# Sheet1.net
KiCad netlist of a schematic drawn in Altium Designer
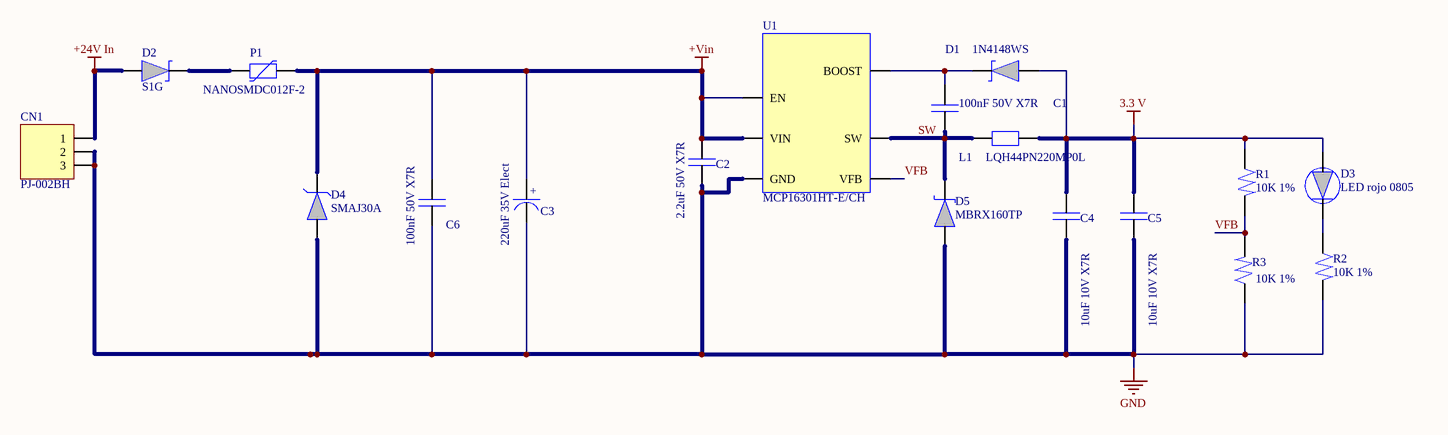
[diagram p0: Sheet1.SchDoc]

(export (version "E")
  (design (tool "Eeschema 10.0.6"))
  (components
    (comp (ref "C1")
      (value "100nF 50V X7R")
      (description "Capacitor AF")
      (libsource (lib "Schlib1") (part "CAPACITOR"))
    )
    (comp (ref "C2")
      (value "2.2uF 50V X7R")
      (description "Capacitor AF")
      (libsource (lib "Schlib1") (part "CAPACITOR"))
    )
    (comp (ref "C3")
      (value "220uF 35V Elect")
      (description "Capacitor polarizado")
      (libsource (lib "Schlib1") (part "POL_CAP"))
    )
    (comp (ref "C4")
      (value "10uF 10V X7R")
      (description "Capacitor AF")
      (libsource (lib "Schlib1") (part "CAPACITOR"))
    )
    (comp (ref "C5")
      (value "10uF 10V X7R")
      (description "Capacitor AF")
      (libsource (lib "Schlib1") (part "CAPACITOR"))
    )
    (comp (ref "C6")
      (value "100nF 50V X7R")
      (description "Capacitor AF")
      (libsource (lib "Schlib1") (part "CAPACITOR"))
    )
    (comp (ref "CN1") (value "PJ-002BH") (libsource (lib "Schlib1") (part "Connector")))
    (comp (ref "D1") (value "1N4148WS") (libsource (lib "Schlib1") (part "TVS_DIODE")))
    (comp (ref "D2") (value "S1G") (libsource (lib "Schlib1") (part "TVS_DIODE")))
    (comp (ref "D3") (value "LED rojo 0805") (libsource (lib "Schlib1") (part "LED_DIODE")))
    (comp (ref "D4") (value "SMAJ30A") (libsource (lib "Schlib1") (part "ZENER_DIODE")))
    (comp (ref "D5") (value "MBRX160TP") (libsource (lib "Schlib1") (part "TVS_DIODE")))
    (comp (ref "L1")
      (value "LQH44PN220MP0L")
      (description "Inductor")
      (libsource (lib "Schlib1") (part "Inductor"))
    )
    (comp (ref "P1")
      (value "NANOSMDC012F-2")
      (description "Polyswitch")
      (libsource (lib "Schlib1") (part "Polyswitch"))
    )
    (comp (ref "R1") (value "10K 1%") (libsource (lib "Schlib1") (part "Resistor")))
    (comp (ref "R2") (value "10K 1%") (libsource (lib "Schlib1") (part "Resistor")))
    (comp (ref "R3") (value "10K 1%") (libsource (lib "Schlib1") (part "Resistor")))
    (comp (ref "U1")
      (value "MCP16301HT-E/CH")
      (description "Driver Switching")
      (libsource (lib "Schlib1") (part "Integrado"))
    )
  )
  (nets
    (net (code "1") (name "+24V In") (class "Default")
      (node (ref "CN1") (pin "42") (pinfunction "1_42") (pintype "passive"))
      (node (ref "D2") (pin "34") (pinfunction "34_34") (pintype "passive"))
    )
    (net (code "2") (name "+Vin") (class "Default")
      (node (ref "C2") (pin "39") (pinfunction "39_39") (pintype "passive"))
      (node (ref "C3") (pin "36") (pinfunction "36_36") (pintype "passive"))
      (node (ref "C6") (pin "39") (pinfunction "39_39") (pintype "passive"))
      (node (ref "D4") (pin "33") (pinfunction "33_33") (pintype "passive"))
      (node (ref "P1") (pin "40") (pinfunction "40_40") (pintype "passive"))
      (node (ref "U1") (pin "49") (pinfunction "EN_49") (pintype "passive"))
      (node (ref "U1") (pin "50") (pinfunction "VIN_50") (pintype "passive"))
    )
    (net (code "3") (name "/SW") (class "Default")
      (node (ref "C1") (pin "38") (pinfunction "38_38") (pintype "passive"))
      (node (ref "D5") (pin "35") (pinfunction "35_35") (pintype "passive"))
      (node (ref "L1") (pin "45") (pinfunction "45_45") (pintype "passive"))
      (node (ref "U1") (pin "52") (pinfunction "SW_52") (pintype "passive"))
    )
    (net (code "4") (name "/VFB") (class "Default")
      (node (ref "R1") (pin "48") (pinfunction "48_48") (pintype "passive"))
      (node (ref "R3") (pin "48") (pinfunction "48_48") (pintype "passive"))
      (node (ref "U1") (pin "54") (pinfunction "VFB_54") (pintype "passive"))
    )
    (net (code "5") (name "3.3 V") (class "Default")
      (node (ref "C4") (pin "39") (pinfunction "39_39") (pintype "passive"))
      (node (ref "C5") (pin "39") (pinfunction "39_39") (pintype "passive"))
      (node (ref "D1") (pin "34") (pinfunction "34_34") (pintype "passive"))
      (node (ref "D3") (pin "31") (pinfunction "31_31") (pintype "passive"))
      (node (ref "L1") (pin "46") (pinfunction "46_46") (pintype "passive"))
      (node (ref "R1") (pin "47") (pinfunction "47_47") (pintype "passive"))
    )
    (net (code "6") (name "GND") (class "Default")
      (node (ref "C2") (pin "38") (pinfunction "38_38") (pintype "passive"))
      (node (ref "C3") (pin "37") (pinfunction "37_37") (pintype "passive"))
      (node (ref "C4") (pin "38") (pinfunction "38_38") (pintype "passive"))
      (node (ref "C5") (pin "38") (pinfunction "38_38") (pintype "passive"))
      (node (ref "C6") (pin "38") (pinfunction "38_38") (pintype "passive"))
      (node (ref "CN1") (pin "43") (pinfunction "2_43") (pintype "passive"))
      (node (ref "CN1") (pin "44") (pinfunction "3_44") (pintype "passive"))
      (node (ref "D4") (pin "32") (pinfunction "32_32") (pintype "passive"))
      (node (ref "D5") (pin "34") (pinfunction "34_34") (pintype "passive"))
      (node (ref "R2") (pin "48") (pinfunction "48_48") (pintype "passive"))
      (node (ref "R3") (pin "47") (pinfunction "47_47") (pintype "passive"))
      (node (ref "U1") (pin "51") (pinfunction "GND_51") (pintype "passive"))
    )
    (net (code "7") (name "Net-(D2-Pad35)") (class "Default")
      (node (ref "D2") (pin "35") (pinfunction "35_35") (pintype "passive"))
      (node (ref "P1") (pin "41") (pinfunction "41_41") (pintype "passive"))
    )
    (net (code "8") (name "Net-(D3-Pad30)") (class "Default")
      (node (ref "D3") (pin "30") (pinfunction "30_30") (pintype "passive"))
      (node (ref "R2") (pin "47") (pinfunction "47_47") (pintype "passive"))
    )
    (net (code "9") (name "Net-(U1-BOOST)") (class "Default")
      (node (ref "C1") (pin "39") (pinfunction "39_39") (pintype "passive"))
      (node (ref "D1") (pin "35") (pinfunction "35_35") (pintype "passive"))
      (node (ref "U1") (pin "53") (pinfunction "BOOST_53") (pintype "passive"))
    )
  )
)
